# SCH_555-led-chaser_2025-11-01.net
KiCad netlist of a schematic drawn in EasyEDA
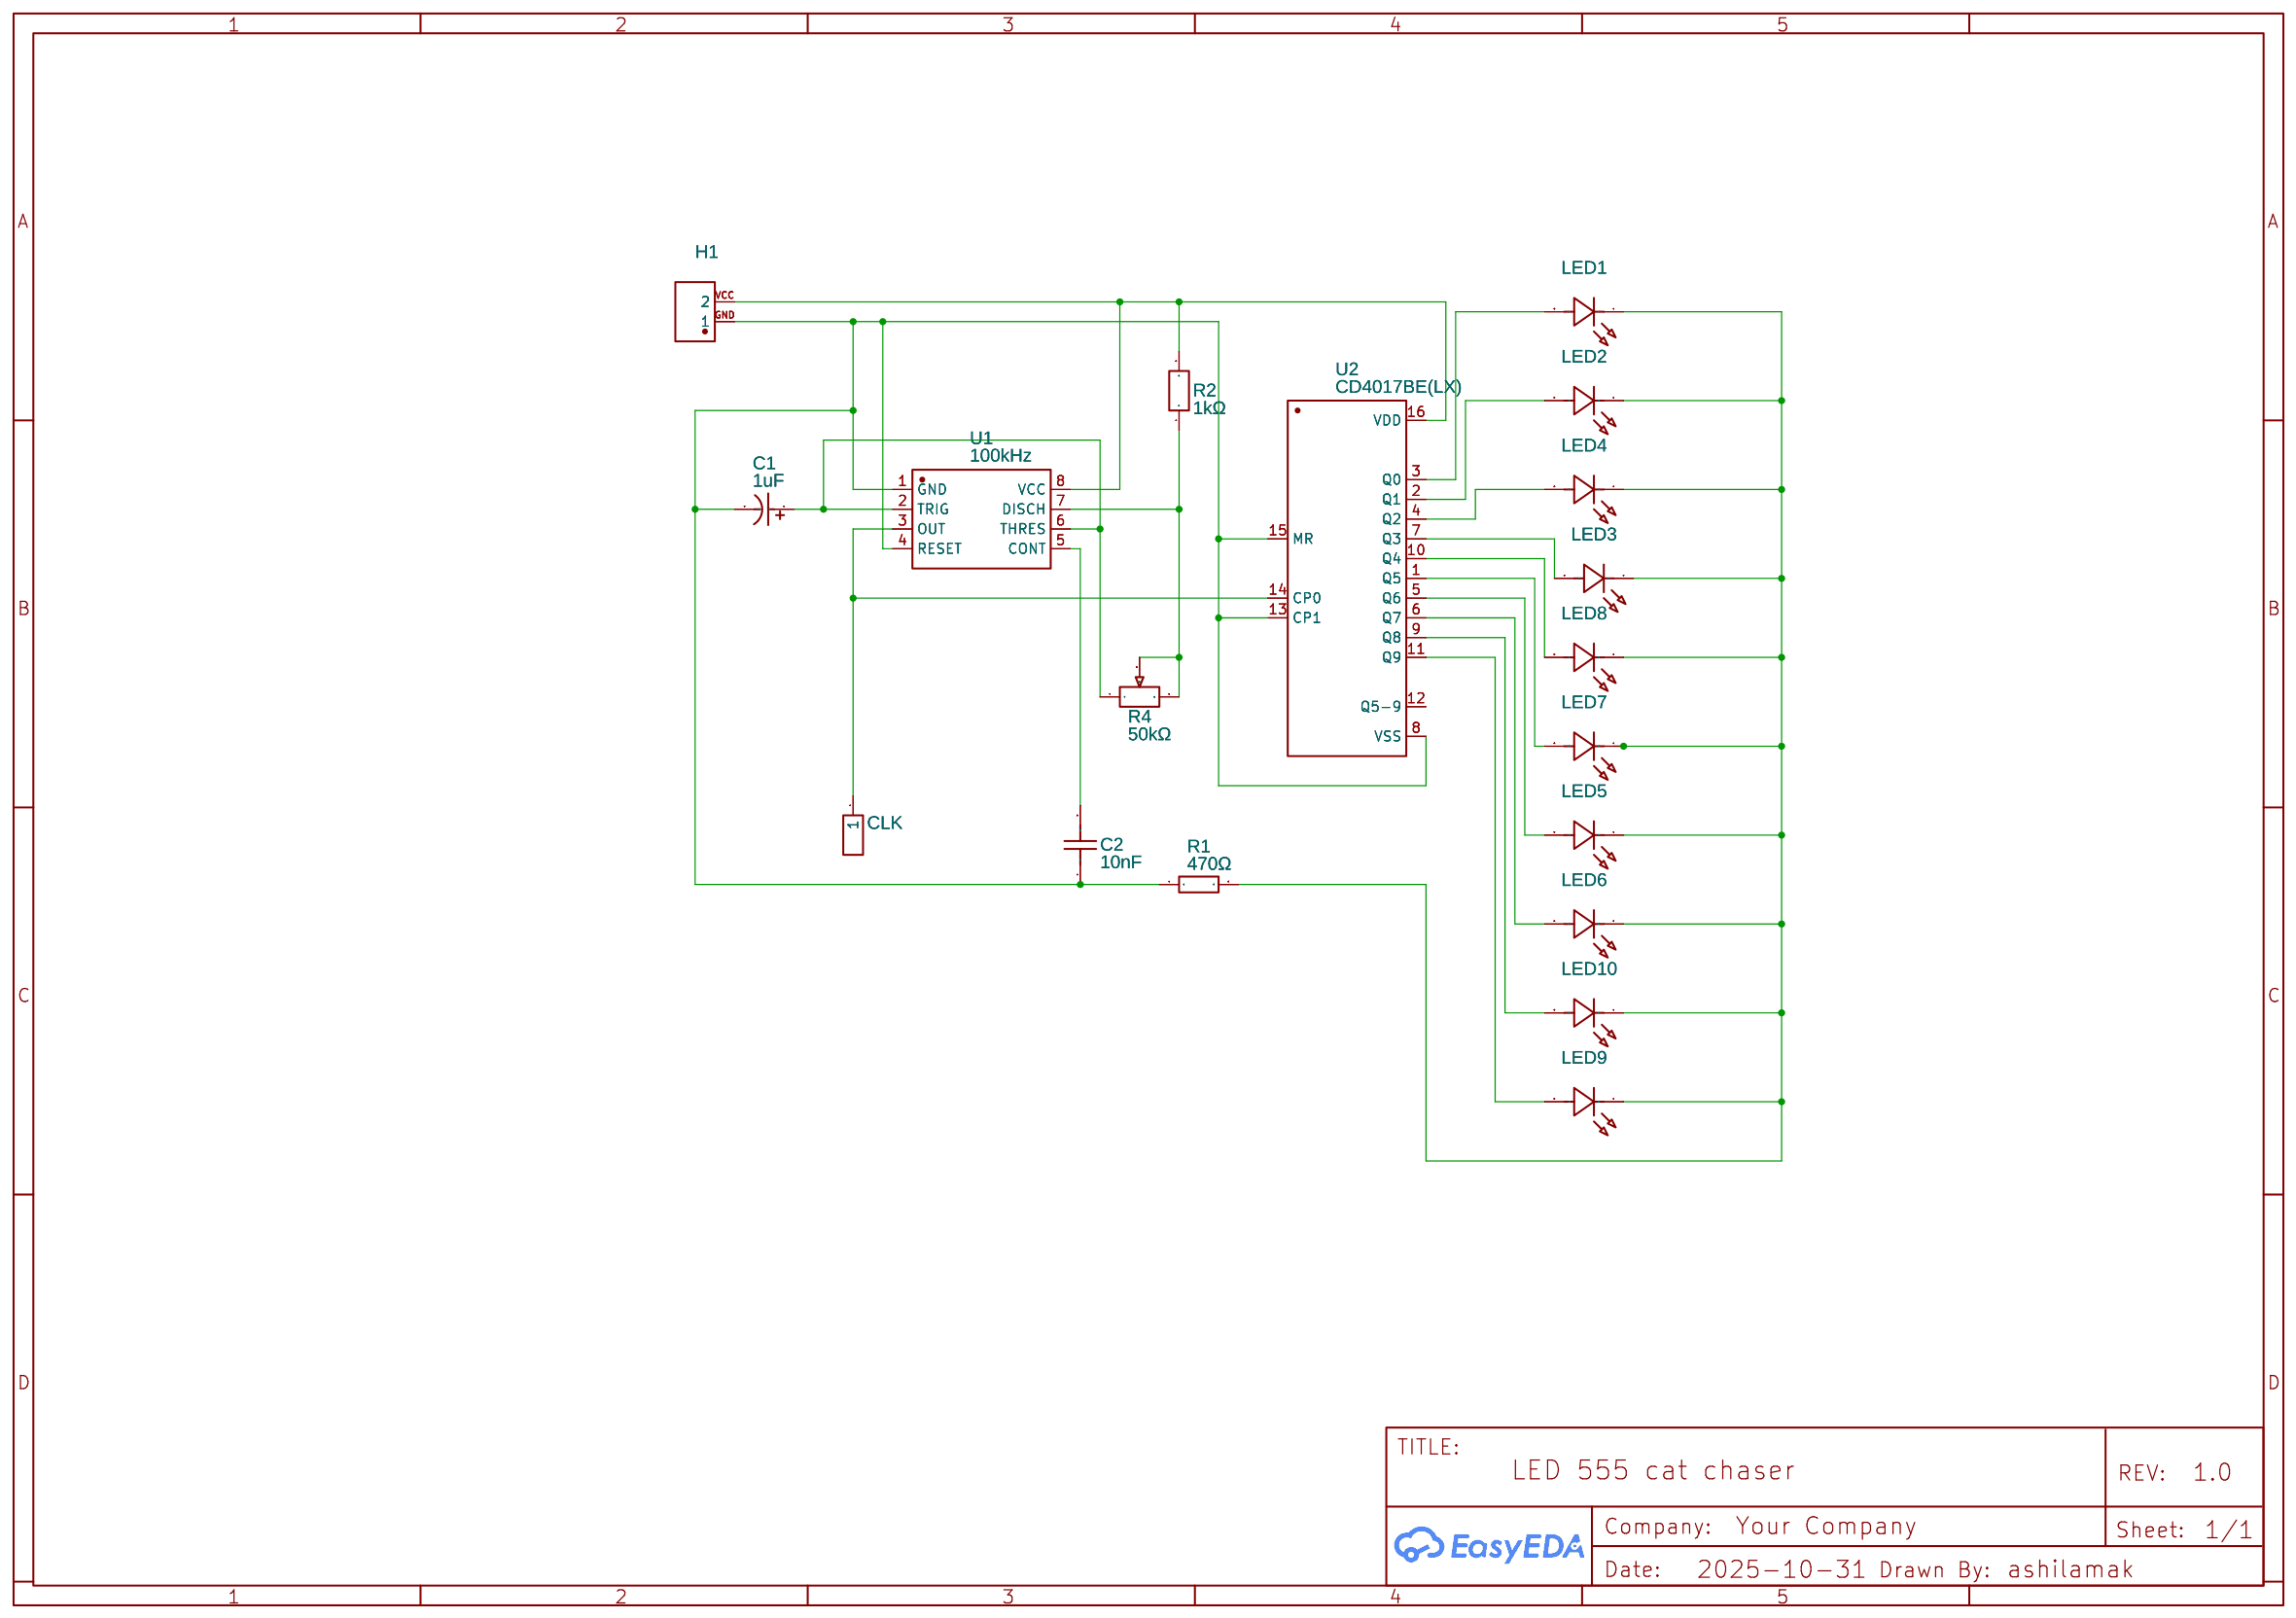
[diagram p0: schematic sheet]

(export (version "E")
  (design (tool "Eeschema 10.0.6"))
  (components
    (comp (ref "C1")
      (value "1uF")
      (fields (field (name "Manufacturer Part") "KF010M050C110A") (field (name "Manufacturer") "CapXon(丰宾)"))
      (libsource (lib "") (part "KF010M050C110A"))
    )
    (comp (ref "C2")
      (value "10nF")
      (fields (field (name "Manufacturer Part") "N09F1B103MN0B0S0N0") (field (name "Manufacturer") "STE(松田)"))
      (libsource (lib "") (part "N09F1B103MN0B0S0N0"))
    )
    (comp (ref "CLK")
      (value "Header-Male-2.54_1x1")
      (fields (field (name "Manufacturer Part") "2.54-1*1P针") (field (name "Manufacturer") "BOOMELE(博穆精密)"))
      (libsource (lib "") (part "Header-Male-2.54_1x1"))
    )
    (comp (ref "H1")
      (value "PZ254V-11-02P")
      (fields (field (name "Manufacturer") "XFCN(兴飞)"))
      (libsource (lib "") (part "PZ254V-11-02P"))
    )
    (comp (ref "LED1")
      (value "L-513LRC-D3")
      (fields (field (name "Manufacturer") "PARALIGHT(光鼎)"))
      (libsource (lib "") (part "L-513LRC-D3"))
    )
    (comp (ref "LED2")
      (value "L-513LRC-D3")
      (fields (field (name "Manufacturer") "PARALIGHT(光鼎)"))
      (libsource (lib "") (part "L-513LRC-D3"))
    )
    (comp (ref "LED3")
      (value "L-513LRC-D3")
      (fields (field (name "Manufacturer") "PARALIGHT(光鼎)"))
      (libsource (lib "") (part "L-513LRC-D3"))
    )
    (comp (ref "LED4")
      (value "L-513LRC-D3")
      (fields (field (name "Manufacturer") "PARALIGHT(光鼎)"))
      (libsource (lib "") (part "L-513LRC-D3"))
    )
    (comp (ref "LED5")
      (value "L-513LRC-D3")
      (fields (field (name "Manufacturer") "PARALIGHT(光鼎)"))
      (libsource (lib "") (part "L-513LRC-D3"))
    )
    (comp (ref "LED6")
      (value "L-513LRC-D3")
      (fields (field (name "Manufacturer") "PARALIGHT(光鼎)"))
      (libsource (lib "") (part "L-513LRC-D3"))
    )
    (comp (ref "LED7")
      (value "L-513LRC-D3")
      (fields (field (name "Manufacturer") "PARALIGHT(光鼎)"))
      (libsource (lib "") (part "L-513LRC-D3"))
    )
    (comp (ref "LED8")
      (value "L-513LRC-D3")
      (fields (field (name "Manufacturer") "PARALIGHT(光鼎)"))
      (libsource (lib "") (part "L-513LRC-D3"))
    )
    (comp (ref "LED9")
      (value "L-513LRC-D3")
      (fields (field (name "Manufacturer") "PARALIGHT(光鼎)"))
      (libsource (lib "") (part "L-513LRC-D3"))
    )
    (comp (ref "LED10")
      (value "L-513LRC-D3")
      (fields (field (name "Manufacturer") "PARALIGHT(光鼎)"))
      (libsource (lib "") (part "L-513LRC-D3"))
    )
    (comp (ref "R1")
      (value "470Ω")
      (fields
        (field (name "Manufacturer Part") "MFR0W4F4700A50")
        (field (name "Manufacturer") "UNI-ROYAL(厚声)")
      )
      (libsource (lib "") (part "MFR0W4F4700A50"))
    )
    (comp (ref "R2")
      (value "1kΩ")
      (fields (field (name "Manufacturer Part") "MF1/4W-1KΩ±1%T52") (field (name "Manufacturer") "华星机电"))
      (libsource (lib "") (part "MF1/4W-1KΩ±1%T52"))
    )
    (comp (ref "R4")
      (value "50kΩ")
      (fields (field (name "Manufacturer Part") "3296X-1-503") (field (name "Manufacturer") "BOCHEN(博晨)"))
      (libsource (lib "") (part "3296X-1-503_C118912"))
    )
    (comp (ref "U1")
      (value "100kHz")
      (fields (field (name "Manufacturer Part") "NE555P") (field (name "Manufacturer") "TI(德州仪器)"))
      (libsource (lib "") (part "NE555P"))
    )
    (comp (ref "U2")
      (value "CD4017BE(LX)")
      (fields (field (name "Manufacturer") "LX(灵星芯微)"))
      (libsource (lib "") (part "CD4017BE(LX)"))
    )
  )
  (nets
    (net (code "1") (name "Net-(H1-1)") (class "Default")
      (node (ref "C1") (pin "2") (pinfunction "2_2") (pintype "input"))
      (node (ref "C2") (pin "1") (pinfunction "1_1") (pintype "unspecified"))
      (node (ref "H1") (pin "GND") (pinfunction "1_GND") (pintype "unspecified"))
      (node (ref "R1") (pin "1") (pinfunction "1_1") (pintype "input"))
      (node (ref "U1") (pin "1") (pinfunction "GND_1") (pintype "unspecified"))
      (node (ref "U1") (pin "4") (pinfunction "RESET_4") (pintype "unspecified"))
      (node (ref "U2") (pin "13") (pinfunction "CP1_13") (pintype "unspecified"))
      (node (ref "U2") (pin "15") (pinfunction "MR_15") (pintype "unspecified"))
      (node (ref "U2") (pin "8") (pinfunction "VSS_8") (pintype "unspecified"))
    )
    (net (code "2") (name "Net-(H1-2)") (class "Default")
      (node (ref "H1") (pin "VCC") (pinfunction "2_VCC") (pintype "unspecified"))
      (node (ref "R2") (pin "2") (pinfunction "2_2") (pintype "unspecified"))
      (node (ref "U1") (pin "8") (pinfunction "VCC_8") (pintype "unspecified"))
      (node (ref "U2") (pin "16") (pinfunction "VDD_16") (pintype "unspecified"))
    )
    (net (code "3") (name "Net-(LED1-A)") (class "Default")
      (node (ref "LED1") (pin "2") (pinfunction "A_2") (pintype "unspecified"))
      (node (ref "U2") (pin "3") (pinfunction "Q0_3") (pintype "unspecified"))
    )
    (net (code "4") (name "Net-(LED1-K)") (class "Default")
      (node (ref "LED1") (pin "1") (pinfunction "K_1") (pintype "unspecified"))
      (node (ref "LED10") (pin "1") (pinfunction "K_1") (pintype "unspecified"))
      (node (ref "LED2") (pin "1") (pinfunction "K_1") (pintype "unspecified"))
      (node (ref "LED3") (pin "1") (pinfunction "K_1") (pintype "unspecified"))
      (node (ref "LED4") (pin "1") (pinfunction "K_1") (pintype "unspecified"))
      (node (ref "LED5") (pin "1") (pinfunction "K_1") (pintype "unspecified"))
      (node (ref "LED6") (pin "1") (pinfunction "K_1") (pintype "unspecified"))
      (node (ref "LED7") (pin "1") (pinfunction "K_1") (pintype "unspecified"))
      (node (ref "LED8") (pin "1") (pinfunction "K_1") (pintype "unspecified"))
      (node (ref "LED9") (pin "1") (pinfunction "K_1") (pintype "unspecified"))
      (node (ref "R1") (pin "2") (pinfunction "2_2") (pintype "input"))
    )
    (net (code "5") (name "Net-(LED2-A)") (class "Default")
      (node (ref "LED2") (pin "2") (pinfunction "A_2") (pintype "unspecified"))
      (node (ref "U2") (pin "2") (pinfunction "Q1_2") (pintype "unspecified"))
    )
    (net (code "6") (name "Net-(LED3-A)") (class "Default")
      (node (ref "LED3") (pin "2") (pinfunction "A_2") (pintype "unspecified"))
      (node (ref "U2") (pin "7") (pinfunction "Q3_7") (pintype "unspecified"))
    )
    (net (code "7") (name "Net-(LED4-A)") (class "Default")
      (node (ref "LED4") (pin "2") (pinfunction "A_2") (pintype "unspecified"))
      (node (ref "U2") (pin "4") (pinfunction "Q2_4") (pintype "unspecified"))
    )
    (net (code "8") (name "Net-(LED5-A)") (class "Default")
      (node (ref "LED5") (pin "2") (pinfunction "A_2") (pintype "unspecified"))
      (node (ref "U2") (pin "5") (pinfunction "Q6_5") (pintype "unspecified"))
    )
    (net (code "9") (name "Net-(LED6-A)") (class "Default")
      (node (ref "LED6") (pin "2") (pinfunction "A_2") (pintype "unspecified"))
      (node (ref "U2") (pin "6") (pinfunction "Q7_6") (pintype "unspecified"))
    )
    (net (code "10") (name "Net-(LED7-A)") (class "Default")
      (node (ref "LED7") (pin "2") (pinfunction "A_2") (pintype "unspecified"))
      (node (ref "U2") (pin "1") (pinfunction "Q5_1") (pintype "unspecified"))
    )
    (net (code "11") (name "Net-(LED8-A)") (class "Default")
      (node (ref "LED8") (pin "2") (pinfunction "A_2") (pintype "unspecified"))
      (node (ref "U2") (pin "10") (pinfunction "Q4_10") (pintype "unspecified"))
    )
    (net (code "12") (name "Net-(LED9-A)") (class "Default")
      (node (ref "LED9") (pin "2") (pinfunction "A_2") (pintype "unspecified"))
      (node (ref "U2") (pin "11") (pinfunction "Q9_11") (pintype "unspecified"))
    )
    (net (code "13") (name "Net-(LED10-A)") (class "Default")
      (node (ref "LED10") (pin "2") (pinfunction "A_2") (pintype "unspecified"))
      (node (ref "U2") (pin "9") (pinfunction "Q8_9") (pintype "unspecified"))
    )
    (net (code "14") (name "Net-(U1-CONT)") (class "Default")
      (node (ref "C2") (pin "2") (pinfunction "2_2") (pintype "unspecified"))
      (node (ref "U1") (pin "5") (pinfunction "CONT_5") (pintype "unspecified"))
    )
    (net (code "15") (name "Net-(U1-DISCH)") (class "Default")
      (node (ref "R2") (pin "1") (pinfunction "1_1") (pintype "unspecified"))
      (node (ref "R4") (pin "2") (pinfunction "2_2") (pintype "input"))
      (node (ref "R4") (pin "3") (pinfunction "3_3") (pintype "input"))
      (node (ref "U1") (pin "7") (pinfunction "DISCH_7") (pintype "unspecified"))
    )
    (net (code "16") (name "Net-(U1-OUT)") (class "Default")
      (node (ref "CLK") (pin "1") (pinfunction "1_1") (pintype "input"))
      (node (ref "U1") (pin "3") (pinfunction "OUT_3") (pintype "unspecified"))
      (node (ref "U2") (pin "14") (pinfunction "CP0_14") (pintype "unspecified"))
    )
    (net (code "17") (name "Net-(U1-THRES)") (class "Default")
      (node (ref "C1") (pin "1") (pinfunction "1_1") (pintype "input"))
      (node (ref "R4") (pin "1") (pinfunction "1_1") (pintype "input"))
      (node (ref "U1") (pin "2") (pinfunction "TRIG_2") (pintype "unspecified"))
      (node (ref "U1") (pin "6") (pinfunction "THRES_6") (pintype "unspecified"))
    )
    (net (code "18") (name "unconnected-(U2-Q5-9-Pad12)") (class "Default")
      (node (ref "U2") (pin "12") (pinfunction "Q5-9_12") (pintype "unspecified"))
    )
  )
)
